# Codec.net
KiCad netlist of a schematic drawn in Altium Designer
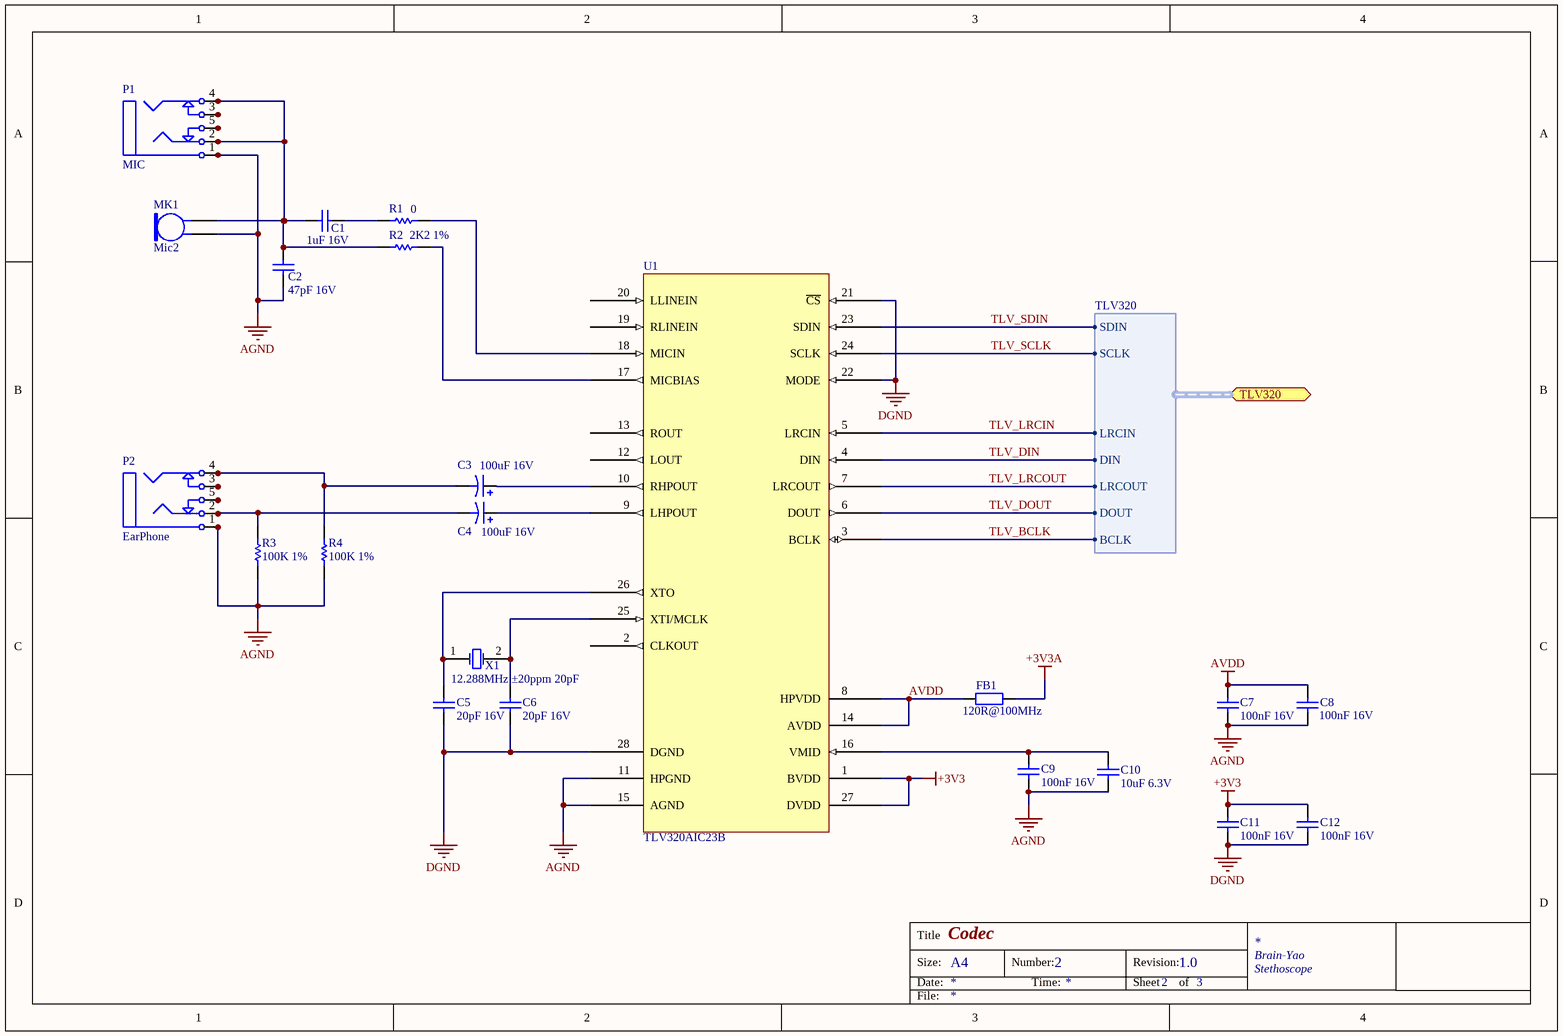
[diagram p0: Codec.SchDoc]

(export (version "E")
  (design (tool "Eeschema 10.0.6"))
  (components
    (comp (ref "C1")
      (value "1uF 16V")
      (footprint "CAPC0603(1608)100_M")
      (description "CAP 1uF 16V ±5% 0603 (1608 Metric) Thickness 1mm SMD")
      (fields (field (name "TOLERANCE") "±5%"))
      (libsource (lib "Altium Content Vault") (part "CMP-1035-02736-1"))
    )
    (comp (ref "C2")
      (value "47pF 16V")
      (footprint "CAPC0603(1608)100_M")
      (description "CAP 47pF 16V ±5% 0603 (1608 Metric) Thickness 1mm SMD")
      (fields (field (name "TOLERANCE") "±5%"))
      (libsource (lib "Altium Content Vault") (part "CAP"))
    )
    (comp (ref "C3")
      (value "100uF 16V")
      (footprint "HONOR_63X54")
      (description "Polarized Capacitor (Radial)")
      (fields (field (name "PUBLISHER") "Altium Limited"))
      (libsource (lib "Miscellaneous Devices") (part "Cap Pol1"))
    )
    (comp (ref "C4")
      (value "100uF 16V")
      (footprint "HONOR_63X54")
      (description "Polarized Capacitor (Radial)")
      (fields (field (name "PUBLISHER") "Altium Limited"))
      (libsource (lib "Miscellaneous Devices") (part "Cap Pol1"))
    )
    (comp (ref "C5")
      (value "20pF 16V")
      (footprint "CAPC0603(1608)100_M")
      (description "CAP 20pF 16V ±0.25pF 0603 (1608 Metric) Thickness 1mm SMD")
      (fields (field (name "TOLERANCE") "±0.25pF"))
      (libsource (lib "Altium Content Vault") (part "CMP-1035-00768-1"))
    )
    (comp (ref "C6")
      (value "20pF 16V")
      (footprint "CAPC0603(1608)100_M")
      (description "CAP 20pF 16V ±0.25pF 0603 (1608 Metric) Thickness 1mm SMD")
      (fields (field (name "TOLERANCE") "±0.25pF"))
      (libsource (lib "Altium Content Vault") (part "CMP-1035-00768-1"))
    )
    (comp (ref "C7")
      (value "100nF 16V")
      (footprint "CAPC0603(1608)100_M")
      (description "CAP 100nF 16V ±10% 0603 (1608 Metric) Thickness 1mm SMD")
      (fields (field (name "TOLERANCE") "±10%"))
      (libsource (lib "Altium Content Vault") (part "CMP-1035-02584-1"))
    )
    (comp (ref "C8")
      (value "100nF 16V")
      (footprint "CAPC0603(1608)100_M")
      (description "CAP 100nF 16V ±10% 0603 (1608 Metric) Thickness 1mm SMD")
      (fields (field (name "TOLERANCE") "±10%"))
      (libsource (lib "Altium Content Vault") (part "CMP-1035-02584-1"))
    )
    (comp (ref "C9")
      (value "100nF 16V")
      (footprint "CAPC0603(1608)100_M")
      (description "CAP 100nF 16V ±10% 0603 (1608 Metric) Thickness 1mm SMD")
      (fields (field (name "TOLERANCE") "±10%"))
      (libsource (lib "Altium Content Vault") (part "CMP-1035-02584-1"))
    )
    (comp (ref "C10")
      (value "10uF 6.3V")
      (footprint "CAPC0603(1608)100_M")
      (description "CAP 10uF 6.3V ±10% 0603 (1608 Metric) Thickness 1mm SMD")
      (fields (field (name "TOLERANCE") "±10%"))
      (libsource (lib "Altium Content Vault") (part "CAP"))
    )
    (comp (ref "C11")
      (value "100nF 16V")
      (footprint "CAPC0603(1608)100_M")
      (description "CAP 100nF 16V ±10% 0603 (1608 Metric) Thickness 1mm SMD")
      (fields (field (name "TOLERANCE") "±10%"))
      (libsource (lib "Altium Content Vault") (part "CMP-1035-02584-1"))
    )
    (comp (ref "C12")
      (value "100nF 16V")
      (footprint "CAPC0603(1608)100_M")
      (description "CAP 100nF 16V ±10% 0603 (1608 Metric) Thickness 1mm SMD")
      (fields (field (name "TOLERANCE") "±10%"))
      (libsource (lib "Altium Content Vault") (part "CMP-1035-02584-1"))
    )
    (comp (ref "FB1")
      (value "120R@100MHz")
      (footprint "RESC1608N")
      (description "Resistor")
      (fields (field (name "PUBLISHER") "Altium Limited"))
      (libsource (lib "Miscellaneous Devices") (part "Res2"))
    )
    (comp (ref "MK1")
      (value "Mic2")
      (footprint "PIN2")
      (description "Microphone")
      (fields (field (name "PUBLISHER") "Altium Limited"))
      (libsource (lib "Miscellaneous Devices") (part "Mic2"))
    )
    (comp (ref "P1")
      (value "MIC")
      (footprint "ST-3150-5N")
      (description "3-Conductor Jack with 2 break contacts (normals) and 2 auxiliary make contacts")
      (fields (field (name "PUBLISHER") "Altium Limited"))
      (libsource (lib "Miscellaneous Connectors") (part "Phonejack Stereo SW"))
    )
    (comp (ref "P2")
      (value "EarPhone")
      (footprint "ST-3150-5N")
      (description "3-Conductor Jack with 2 break contacts (normals) and 2 auxiliary make contacts")
      (fields (field (name "PUBLISHER") "Altium Limited"))
      (libsource (lib "Miscellaneous Connectors") (part "Phonejack Stereo SW"))
    )
    (comp (ref "R1")
      (value "0")
      (footprint "RESC0603(1608)_M")
      (description "Jumper 0603 (1608 Metric)")
      (fields (field (name "POWER") "None"))
      (libsource (lib "Altium Content Vault") (part "RES"))
    )
    (comp (ref "R2")
      (value "2K2 1%")
      (footprint "RESC0603(1608)_M")
      (description "2K2 0.1W 1% 0603 (1608 Metric)  SMD")
      (fields (field (name "TOLERANCE") "1 %") (field (name "POWER") "0.1 W"))
      (libsource (lib "Altium Content Vault") (part "CMP-1012-00546-1"))
    )
    (comp (ref "R3")
      (value "100K 1%")
      (footprint "RESC0603(1608)_M")
      (description "100K 0.1W 1% 0603 (1608 Metric)  SMD")
      (fields (field (name "POWER") "0.1 W") (field (name "TOLERANCE") "1 %"))
      (libsource (lib "Altium Content Vault") (part "RES"))
    )
    (comp (ref "R4")
      (value "100K 1%")
      (footprint "RESC0603(1608)_M")
      (description "100K 0.1W 1% 0603 (1608 Metric)  SMD")
      (fields (field (name "POWER") "0.1 W") (field (name "TOLERANCE") "1 %"))
      (libsource (lib "Altium Content Vault") (part "RES"))
    )
    (comp (ref "U1")
      (value "TLV320AIC23B")
      (footprint "PW28")
      (description "Imported")
      (fields
        (field (name "MANUFACTURER_PART_NUMBER") "tlv320aic23b_pw_28")
        (field (name "MANUFACTURER") "Texas Instruments")
      )
      (libsource (lib "Schlib") (part "TLV320AIC23B"))
    )
    (comp (ref "X1")
      (value "12.288MHz ±20ppm 20pF")
      (footprint "49S")
      (description "Crystal Oscillator")
      (fields (field (name "PUBLISHER") "Altium Limited"))
      (libsource (lib "Miscellaneous Devices") (part "XTAL"))
    )
  )
  (nets
    (net (code "2") (name "+3V3") (class "Default")
      (node (ref "C11") (pin "2") (pinfunction "2_2") (pintype "passive"))
      (node (ref "C12") (pin "2") (pinfunction "2_2") (pintype "passive"))
      (node (ref "U1") (pin "1") (pinfunction "BVDD_1") (pintype "power_in"))
      (node (ref "U1") (pin "27") (pinfunction "DVDD_27") (pintype "power_in"))
    )
    (net (code "3") (name "+3V3A") (class "Default")
      (node (ref "FB1") (pin "2") (pinfunction "2_2") (pintype "passive"))
    )
    (net (code "4") (name "/TLV_BCLK") (class "Default")
      (node (ref "U1") (pin "3") (pinfunction "BCLK_3") (pintype "bidirectional"))
    )
    (net (code "5") (name "/TLV_DIN") (class "Default")
      (node (ref "U1") (pin "4") (pinfunction "DIN_4") (pintype "input"))
    )
    (net (code "6") (name "/TLV_DOUT") (class "Default")
      (node (ref "U1") (pin "6") (pinfunction "DOUT_6") (pintype "output"))
    )
    (net (code "7") (name "/TLV_LRCIN") (class "Default")
      (node (ref "U1") (pin "5") (pinfunction "LRCIN_5") (pintype "input"))
    )
    (net (code "8") (name "/TLV_LRCOUT") (class "Default")
      (node (ref "U1") (pin "7") (pinfunction "LRCOUT_7") (pintype "output"))
    )
    (net (code "9") (name "/TLV_SCLK") (class "Default")
      (node (ref "U1") (pin "24") (pinfunction "SCLK_24") (pintype "input"))
    )
    (net (code "10") (name "/TLV_SDIN") (class "Default")
      (node (ref "U1") (pin "23") (pinfunction "SDIN_23") (pintype "input"))
    )
    (net (code "12") (name "AGND") (class "Default")
      (node (ref "C10") (pin "1") (pinfunction "1_1") (pintype "passive"))
      (node (ref "C2") (pin "1") (pinfunction "1_1") (pintype "passive"))
      (node (ref "C7") (pin "1") (pinfunction "1_1") (pintype "passive"))
      (node (ref "C8") (pin "1") (pinfunction "1_1") (pintype "passive"))
      (node (ref "C9") (pin "1") (pinfunction "1_1") (pintype "passive"))
      (node (ref "MK1") (pin "2") (pinfunction "2_2") (pintype "passive"))
      (node (ref "P1") (pin "1") (pinfunction "1_1") (pintype "passive"))
      (node (ref "P1") (pin "1A") (pinfunction "1A_1A") (pintype "passive"))
      (node (ref "P1") (pin "1B") (pinfunction "1B_1B") (pintype "passive"))
      (node (ref "P2") (pin "1") (pinfunction "1_1") (pintype "passive"))
      (node (ref "P2") (pin "1A") (pinfunction "1A_1A") (pintype "passive"))
      (node (ref "P2") (pin "1B") (pinfunction "1B_1B") (pintype "passive"))
      (node (ref "R3") (pin "1") (pinfunction "1_1") (pintype "passive"))
      (node (ref "R4") (pin "1") (pinfunction "1_1") (pintype "passive"))
      (node (ref "U1") (pin "11") (pinfunction "HPGND_11") (pintype "power_in"))
      (node (ref "U1") (pin "15") (pinfunction "AGND_15") (pintype "power_in"))
    )
    (net (code "13") (name "AVDD") (class "Default")
      (node (ref "C7") (pin "2") (pinfunction "2_2") (pintype "passive"))
      (node (ref "C8") (pin "2") (pinfunction "2_2") (pintype "passive"))
      (node (ref "FB1") (pin "1") (pinfunction "1_1") (pintype "passive"))
      (node (ref "U1") (pin "14") (pinfunction "AVDD_14") (pintype "power_in"))
      (node (ref "U1") (pin "8") (pinfunction "HPVDD_8") (pintype "power_in"))
    )
    (net (code "14") (name "DGND") (class "Default")
      (node (ref "C11") (pin "1") (pinfunction "1_1") (pintype "passive"))
      (node (ref "C12") (pin "1") (pinfunction "1_1") (pintype "passive"))
      (node (ref "C5") (pin "1") (pinfunction "1_1") (pintype "passive"))
      (node (ref "C6") (pin "1") (pinfunction "1_1") (pintype "passive"))
      (node (ref "U1") (pin "21") (pinfunction "CS_21") (pintype "input"))
      (node (ref "U1") (pin "22") (pinfunction "MODE_22") (pintype "input"))
      (node (ref "U1") (pin "28") (pinfunction "DGND_28") (pintype "power_in"))
    )
    (net (code "15") (name "Net-(C1-Pad1)") (class "Default")
      (node (ref "C1") (pin "1") (pinfunction "1_1") (pintype "passive"))
      (node (ref "C2") (pin "2") (pinfunction "2_2") (pintype "passive"))
      (node (ref "MK1") (pin "1") (pinfunction "1_1") (pintype "passive"))
      (node (ref "P1") (pin "2") (pinfunction "2_2") (pintype "passive"))
      (node (ref "P1") (pin "2A") (pinfunction "2A_2A") (pintype "passive"))
      (node (ref "P1") (pin "2B") (pinfunction "2B_2B") (pintype "passive"))
      (node (ref "P1") (pin "4") (pinfunction "4_4") (pintype "passive"))
      (node (ref "P1") (pin "4A") (pinfunction "4A_4A") (pintype "passive"))
      (node (ref "P1") (pin "4B") (pinfunction "4B_4B") (pintype "passive"))
      (node (ref "R2") (pin "1") (pinfunction "1_1") (pintype "passive"))
    )
    (net (code "16") (name "Net-(C1-Pad2)") (class "Default")
      (node (ref "C1") (pin "2") (pinfunction "2_2") (pintype "passive"))
      (node (ref "R1") (pin "1") (pinfunction "1_1") (pintype "passive"))
    )
    (net (code "17") (name "Net-(C3-Pad2)") (class "Default")
      (node (ref "C3") (pin "2") (pinfunction "2_2") (pintype "passive"))
      (node (ref "P2") (pin "4") (pinfunction "4_4") (pintype "passive"))
      (node (ref "P2") (pin "4A") (pinfunction "4A_4A") (pintype "passive"))
      (node (ref "P2") (pin "4B") (pinfunction "4B_4B") (pintype "passive"))
      (node (ref "R4") (pin "2") (pinfunction "2_2") (pintype "passive"))
    )
    (net (code "18") (name "Net-(C4-Pad2)") (class "Default")
      (node (ref "C4") (pin "2") (pinfunction "2_2") (pintype "passive"))
      (node (ref "P2") (pin "2") (pinfunction "2_2") (pintype "passive"))
      (node (ref "P2") (pin "2A") (pinfunction "2A_2A") (pintype "passive"))
      (node (ref "P2") (pin "2B") (pinfunction "2B_2B") (pintype "passive"))
      (node (ref "R3") (pin "2") (pinfunction "2_2") (pintype "passive"))
    )
    (net (code "19") (name "Net-(P1-Pad3)") (class "Default")
      (node (ref "P1") (pin "3") (pinfunction "3_3") (pintype "passive"))
      (node (ref "P1") (pin "3A") (pinfunction "3A_3A") (pintype "passive"))
      (node (ref "P1") (pin "3B") (pinfunction "3B_3B") (pintype "passive"))
    )
    (net (code "20") (name "Net-(P1-Pad5)") (class "Default")
      (node (ref "P1") (pin "5") (pinfunction "5_5") (pintype "passive"))
      (node (ref "P1") (pin "5A") (pinfunction "5A_5A") (pintype "passive"))
      (node (ref "P1") (pin "5B") (pinfunction "5B_5B") (pintype "passive"))
    )
    (net (code "21") (name "Net-(P2-Pad3)") (class "Default")
      (node (ref "P2") (pin "3") (pinfunction "3_3") (pintype "passive"))
      (node (ref "P2") (pin "3A") (pinfunction "3A_3A") (pintype "passive"))
      (node (ref "P2") (pin "3B") (pinfunction "3B_3B") (pintype "passive"))
    )
    (net (code "22") (name "Net-(P2-Pad5)") (class "Default")
      (node (ref "P2") (pin "5") (pinfunction "5_5") (pintype "passive"))
      (node (ref "P2") (pin "5A") (pinfunction "5A_5A") (pintype "passive"))
      (node (ref "P2") (pin "5B") (pinfunction "5B_5B") (pintype "passive"))
    )
    (net (code "23") (name "Net-(U1-LHPOUT)") (class "Default")
      (node (ref "C4") (pin "1") (pinfunction "1_1") (pintype "passive"))
      (node (ref "U1") (pin "9") (pinfunction "LHPOUT_9") (pintype "output"))
    )
    (net (code "24") (name "Net-(U1-MICBIAS)") (class "Default")
      (node (ref "R2") (pin "2") (pinfunction "2_2") (pintype "passive"))
      (node (ref "U1") (pin "17") (pinfunction "MICBIAS_17") (pintype "output"))
    )
    (net (code "25") (name "Net-(U1-MICIN)") (class "Default")
      (node (ref "R1") (pin "2") (pinfunction "2_2") (pintype "passive"))
      (node (ref "U1") (pin "18") (pinfunction "MICIN_18") (pintype "input"))
    )
    (net (code "26") (name "Net-(U1-RHPOUT)") (class "Default")
      (node (ref "C3") (pin "1") (pinfunction "1_1") (pintype "passive"))
      (node (ref "U1") (pin "10") (pinfunction "RHPOUT_10") (pintype "output"))
    )
    (net (code "27") (name "Net-(U1-VMID)") (class "Default")
      (node (ref "C10") (pin "2") (pinfunction "2_2") (pintype "passive"))
      (node (ref "C9") (pin "2") (pinfunction "2_2") (pintype "passive"))
      (node (ref "U1") (pin "16") (pinfunction "VMID_16") (pintype "input"))
    )
    (net (code "28") (name "Net-(U1-XTI{slash}MCLK)") (class "Default")
      (node (ref "C6") (pin "2") (pinfunction "2_2") (pintype "passive"))
      (node (ref "U1") (pin "25") (pinfunction "XTI/MCLK_25") (pintype "input"))
      (node (ref "X1") (pin "2") (pinfunction "OSC2_2") (pintype "passive"))
    )
    (net (code "29") (name "Net-(U1-XTO)") (class "Default")
      (node (ref "C5") (pin "2") (pinfunction "2_2") (pintype "passive"))
      (node (ref "U1") (pin "26") (pinfunction "XTO_26") (pintype "output"))
      (node (ref "X1") (pin "1") (pinfunction "OSC1_1") (pintype "passive"))
    )
    (net (code "30") (name "unconnected-(U1-CLKOUT-Pad2)") (class "Default")
      (node (ref "U1") (pin "2") (pinfunction "CLKOUT_2") (pintype "output"))
    )
    (net (code "31") (name "unconnected-(U1-LLINEIN-Pad20)") (class "Default")
      (node (ref "U1") (pin "20") (pinfunction "LLINEIN_20") (pintype "input"))
    )
    (net (code "32") (name "unconnected-(U1-LOUT-Pad12)") (class "Default")
      (node (ref "U1") (pin "12") (pinfunction "LOUT_12") (pintype "output"))
    )
    (net (code "33") (name "unconnected-(U1-RLINEIN-Pad19)") (class "Default")
      (node (ref "U1") (pin "19") (pinfunction "RLINEIN_19") (pintype "input"))
    )
    (net (code "34") (name "unconnected-(U1-ROUT-Pad13)") (class "Default")
      (node (ref "U1") (pin "13") (pinfunction "ROUT_13") (pintype "output"))
    )
  )
)
